# ESP8266.net
KiCad netlist of a schematic drawn in EAGLE
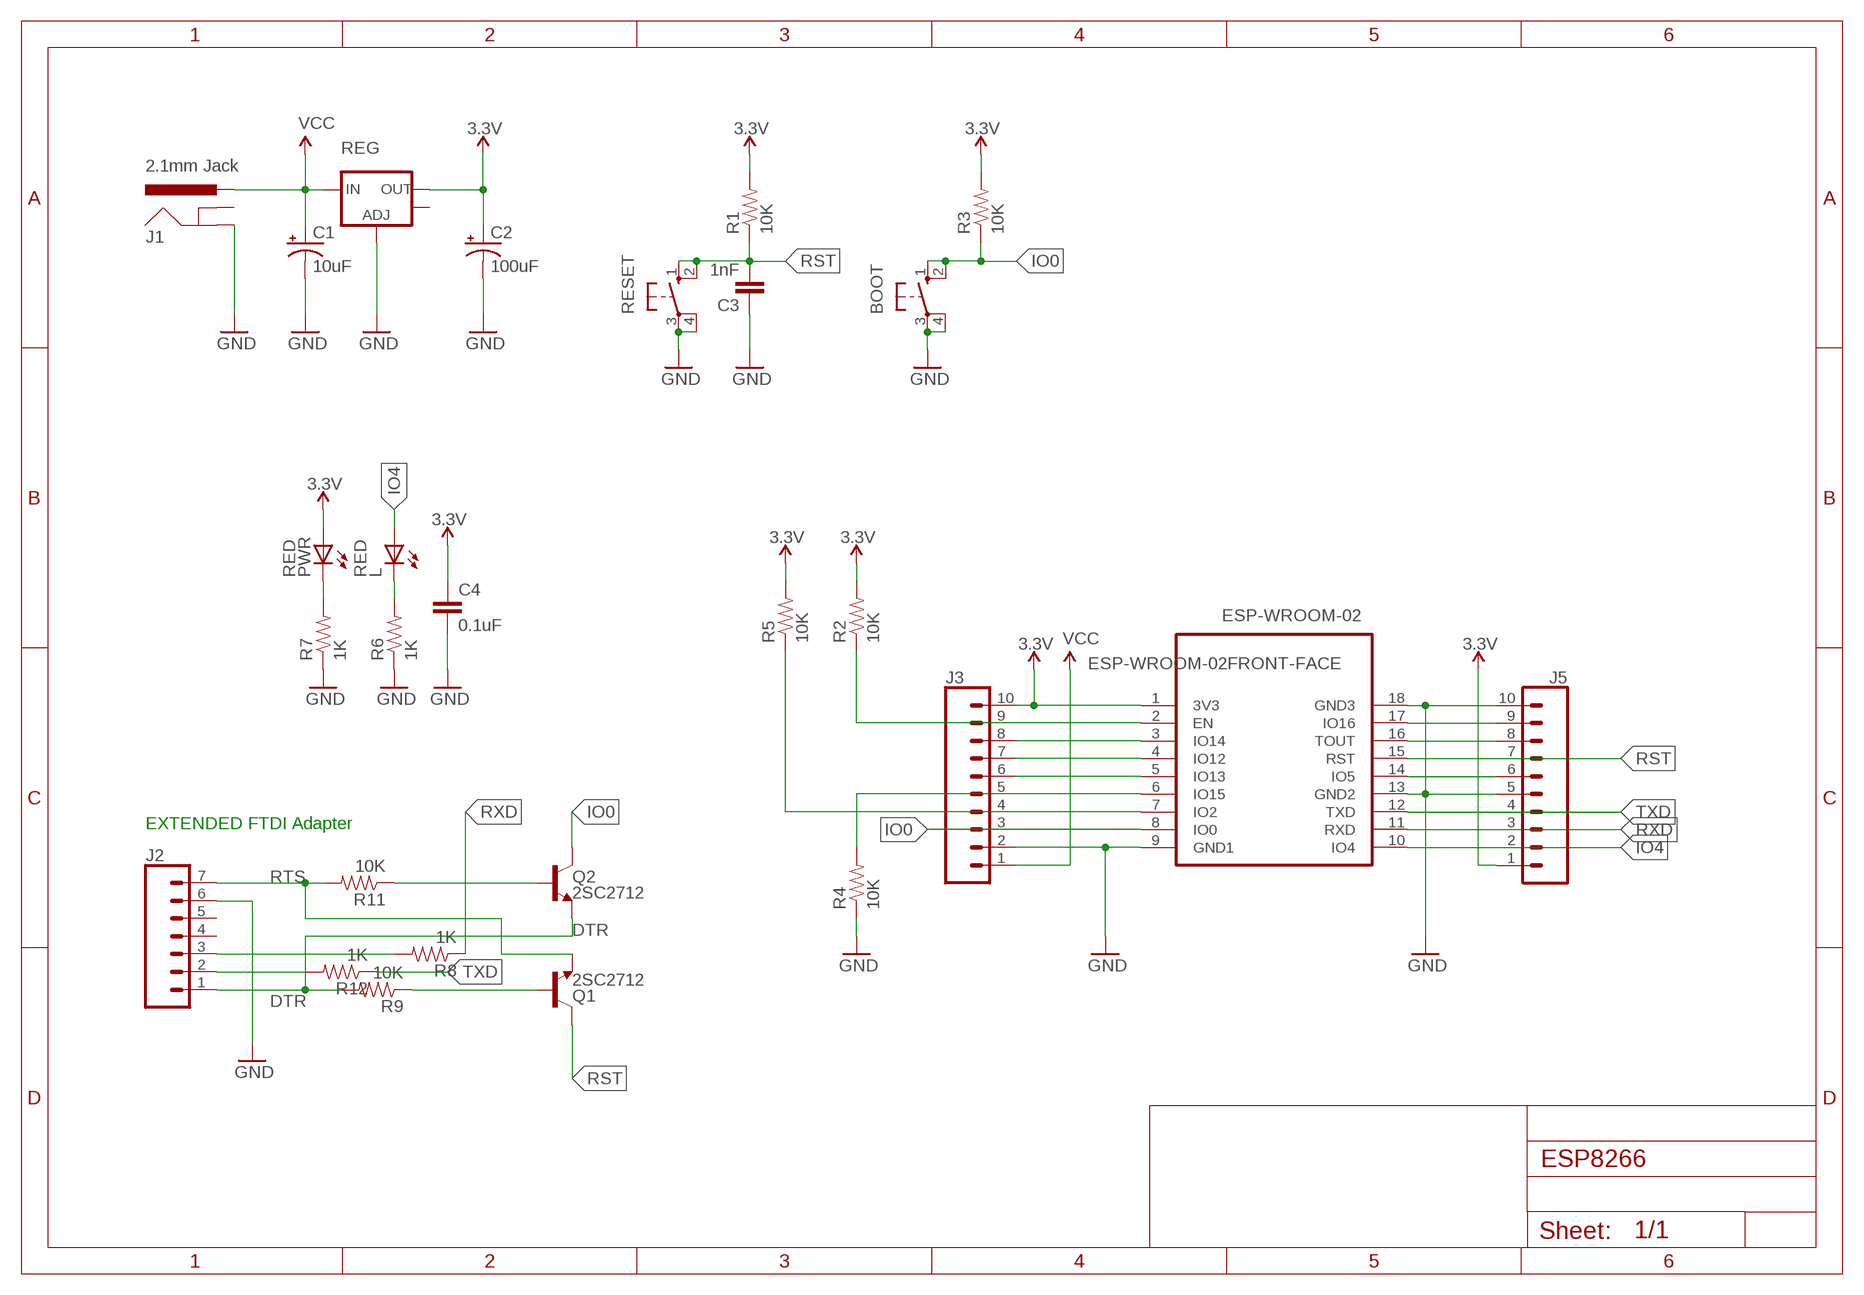
[diagram p0: schematic, sheet 1]

(export (version "E")
  (design (tool "Eeschema 10.0.6"))
  (components
    (comp (ref "BOOT")
      (value "10-XX")
      (footprint "eagle-import:B3F-10XX")
      (libsource (lib "eagle-import") (part "10-XX"))
    )
    (comp (ref "C1")
      (value "10uF")
      (footprint "eagle-import:PANASONIC_D")
      (libsource (lib "eagle-import") (part "CAP_POLD"))
    )
    (comp (ref "C2")
      (value "100uF")
      (footprint "eagle-import:PANASONIC_D")
      (libsource (lib "eagle-import") (part "CAP_POLD"))
    )
    (comp (ref "C3")
      (value "1nF")
      (footprint "eagle-import:0805")
      (libsource (lib "eagle-import") (part "CAP0805"))
    )
    (comp (ref "C4")
      (value "0.1uF")
      (footprint "eagle-import:0805")
      (libsource (lib "eagle-import") (part "CAP0805"))
    )
    (comp (ref "ESP-WROOM-02")
      (value "ESP-WROOM-02FRONT-FACE")
      (footprint "eagle-import:FRONT-FACE")
      (libsource (lib "eagle-import") (part "ESP-WROOM-02FRONT-FACE"))
    )
    (comp (ref "J1")
      (value "2.1mm Jack")
      (footprint "eagle-import:POWER_JACK_PTH_LOCK")
      (libsource (lib "eagle-import") (part "POWER_JACKPTH_LOCK"))
    )
    (comp (ref "J2")
      (value "CONN_07LOCK")
      (footprint "eagle-import:1X07_LOCK")
      (libsource (lib "eagle-import") (part "CONN_07LOCK"))
    )
    (comp (ref "J3")
      (value "CONN_10\"")
      (footprint "eagle-import:1X10")
      (libsource (lib "eagle-import") (part "CONN_10{dblquote}"))
    )
    (comp (ref "J5")
      (value "CONN_10\"")
      (footprint "eagle-import:1X10")
      (libsource (lib "eagle-import") (part "CONN_10{dblquote}"))
    )
    (comp (ref "L")
      (value "RED")
      (footprint "eagle-import:CHIP-LED0805")
      (libsource (lib "eagle-import") (part "LEDCHIP-LED0805"))
    )
    (comp (ref "PWR")
      (value "RED")
      (footprint "eagle-import:CHIP-LED0805")
      (libsource (lib "eagle-import") (part "LEDCHIP-LED0805"))
    )
    (comp (ref "Q1")
      (value "2SC2712")
      (footprint "eagle-import:SOT23-3")
      (libsource (lib "eagle-import") (part "TRANS_NPN-MMBTA42"))
    )
    (comp (ref "Q2")
      (value "2SC2712")
      (footprint "eagle-import:SOT23-3")
      (libsource (lib "eagle-import") (part "TRANS_NPN-MMBTA42"))
    )
    (comp (ref "R1")
      (value "10K")
      (footprint "eagle-import:0805")
      (libsource (lib "eagle-import") (part "RESISTOR0805-RES"))
    )
    (comp (ref "R2")
      (value "10K")
      (footprint "eagle-import:0805")
      (libsource (lib "eagle-import") (part "RESISTOR0805-RES"))
    )
    (comp (ref "R3")
      (value "10K")
      (footprint "eagle-import:0805")
      (libsource (lib "eagle-import") (part "RESISTOR0805-RES"))
    )
    (comp (ref "R4")
      (value "10K")
      (footprint "eagle-import:0805")
      (libsource (lib "eagle-import") (part "RESISTOR0805-RES"))
    )
    (comp (ref "R5")
      (value "10K")
      (footprint "eagle-import:0805")
      (libsource (lib "eagle-import") (part "RESISTOR0805-RES"))
    )
    (comp (ref "R6")
      (value "1K")
      (footprint "eagle-import:0805")
      (libsource (lib "eagle-import") (part "RESISTOR0805-RES"))
    )
    (comp (ref "R7")
      (value "1K")
      (footprint "eagle-import:0805")
      (libsource (lib "eagle-import") (part "RESISTOR0805-RES"))
    )
    (comp (ref "R8")
      (value "1K")
      (footprint "eagle-import:0805")
      (libsource (lib "eagle-import") (part "RESISTOR0805-RES"))
    )
    (comp (ref "R9")
      (value "10K")
      (footprint "eagle-import:0805")
      (libsource (lib "eagle-import") (part "RESISTOR0805-RES"))
    )
    (comp (ref "R11")
      (value "10K")
      (footprint "eagle-import:0805")
      (libsource (lib "eagle-import") (part "RESISTOR0805-RES"))
    )
    (comp (ref "R12")
      (value "1K")
      (footprint "eagle-import:0805")
      (libsource (lib "eagle-import") (part "RESISTOR0805-RES"))
    )
    (comp (ref "REG")
      (value "V_REG_LM1117SOT223")
      (footprint "eagle-import:SOT223")
      (libsource (lib "eagle-import") (part "V_REG_LM1117SOT223"))
    )
    (comp (ref "RESET")
      (value "10-XX")
      (footprint "eagle-import:B3F-10XX")
      (libsource (lib "eagle-import") (part "10-XX"))
    )
  )
  (nets
    (net (code "1") (name "/DTR") (class "Default")
      (node (ref "J2") (pin "1") (pinfunction "1_1") (pintype "passive"))
      (node (ref "Q2") (pin "2") (pinfunction "E_2") (pintype "passive"))
      (node (ref "R9") (pin "2") (pinfunction "2_2") (pintype "passive"))
    )
    (net (code "2") (name "/RTS") (class "Default")
      (node (ref "J2") (pin "7") (pinfunction "7_7") (pintype "passive"))
      (node (ref "Q1") (pin "2") (pinfunction "E_2") (pintype "passive"))
      (node (ref "R11") (pin "2") (pinfunction "2_2") (pintype "passive"))
    )
    (net (code "3") (name "3.3V") (class "Default")
      (node (ref "C2") (pin "+") (pinfunction "+_+") (pintype "passive"))
      (node (ref "C4") (pin "1") (pinfunction "1_1") (pintype "passive"))
      (node (ref "ESP-WROOM-02") (pin "1") (pinfunction "3V3_1") (pintype "power_in"))
      (node (ref "J3") (pin "10") (pinfunction "10_10") (pintype "passive"))
      (node (ref "J5") (pin "1") (pinfunction "1_1") (pintype "passive"))
      (node (ref "PWR") (pin "A") (pinfunction "A_A") (pintype "passive"))
      (node (ref "R1") (pin "2") (pinfunction "2_2") (pintype "passive"))
      (node (ref "R2") (pin "2") (pinfunction "2_2") (pintype "passive"))
      (node (ref "R3") (pin "2") (pinfunction "2_2") (pintype "passive"))
      (node (ref "R5") (pin "2") (pinfunction "2_2") (pintype "passive"))
      (node (ref "REG") (pin "2") (pinfunction "OUT_2") (pintype "output"))
    )
    (net (code "4") (name "GND") (class "Default")
      (node (ref "BOOT") (pin "3") (pinfunction "P_3") (pintype "passive"))
      (node (ref "BOOT") (pin "4") (pinfunction "P1_4") (pintype "passive"))
      (node (ref "C1") (pin "-") (pinfunction "-_-") (pintype "passive"))
      (node (ref "C2") (pin "-") (pinfunction "-_-") (pintype "passive"))
      (node (ref "C3") (pin "1") (pinfunction "1_1") (pintype "passive"))
      (node (ref "C4") (pin "2") (pinfunction "2_2") (pintype "passive"))
      (node (ref "ESP-WROOM-02") (pin "13") (pinfunction "GND2_13") (pintype "power_in"))
      (node (ref "ESP-WROOM-02") (pin "18") (pinfunction "GND3_18") (pintype "power_in"))
      (node (ref "ESP-WROOM-02") (pin "9") (pinfunction "GND1_9") (pintype "power_in"))
      (node (ref "J1") (pin "GND") (pinfunction "GND_GND") (pintype "bidirectional"))
      (node (ref "J2") (pin "6") (pinfunction "6_6") (pintype "passive"))
      (node (ref "J3") (pin "2") (pinfunction "2_2") (pintype "passive"))
      (node (ref "J5") (pin "10") (pinfunction "10_10") (pintype "passive"))
      (node (ref "J5") (pin "5") (pinfunction "5_5") (pintype "passive"))
      (node (ref "R4") (pin "1") (pinfunction "1_1") (pintype "passive"))
      (node (ref "R6") (pin "1") (pinfunction "1_1") (pintype "passive"))
      (node (ref "R7") (pin "1") (pinfunction "1_1") (pintype "passive"))
      (node (ref "REG") (pin "1") (pinfunction "ADJ_1") (pintype "input"))
      (node (ref "RESET") (pin "3") (pinfunction "P_3") (pintype "passive"))
      (node (ref "RESET") (pin "4") (pinfunction "P1_4") (pintype "passive"))
    )
    (net (code "5") (name "IO0") (class "Default")
      (node (ref "BOOT") (pin "1") (pinfunction "S_1") (pintype "passive"))
      (node (ref "BOOT") (pin "2") (pinfunction "S1_2") (pintype "passive"))
      (node (ref "ESP-WROOM-02") (pin "8") (pinfunction "IO0_8") (pintype "bidirectional"))
      (node (ref "J3") (pin "3") (pinfunction "3_3") (pintype "passive"))
      (node (ref "Q2") (pin "3") (pinfunction "C_3") (pintype "passive"))
      (node (ref "R3") (pin "1") (pinfunction "1_1") (pintype "passive"))
    )
    (net (code "6") (name "IO4") (class "Default")
      (node (ref "ESP-WROOM-02") (pin "10") (pinfunction "IO4_10") (pintype "bidirectional"))
      (node (ref "J5") (pin "2") (pinfunction "2_2") (pintype "passive"))
      (node (ref "L") (pin "A") (pinfunction "A_A") (pintype "passive"))
    )
    (net (code "7") (name "Net-(ESP-WROOM-02-EN)") (class "Default")
      (node (ref "ESP-WROOM-02") (pin "2") (pinfunction "EN_2") (pintype "bidirectional"))
      (node (ref "J3") (pin "9") (pinfunction "9_9") (pintype "passive"))
      (node (ref "R2") (pin "1") (pinfunction "1_1") (pintype "passive"))
    )
    (net (code "8") (name "Net-(ESP-WROOM-02-IO2)") (class "Default")
      (node (ref "ESP-WROOM-02") (pin "7") (pinfunction "IO2_7") (pintype "bidirectional"))
      (node (ref "J3") (pin "4") (pinfunction "4_4") (pintype "passive"))
      (node (ref "R5") (pin "1") (pinfunction "1_1") (pintype "passive"))
    )
    (net (code "9") (name "Net-(ESP-WROOM-02-IO5)") (class "Default")
      (node (ref "ESP-WROOM-02") (pin "14") (pinfunction "IO5_14") (pintype "open_collector"))
      (node (ref "J5") (pin "6") (pinfunction "6_6") (pintype "passive"))
    )
    (net (code "10") (name "Net-(ESP-WROOM-02-IO12)") (class "Default")
      (node (ref "ESP-WROOM-02") (pin "4") (pinfunction "IO12_4") (pintype "bidirectional"))
      (node (ref "J3") (pin "7") (pinfunction "7_7") (pintype "passive"))
    )
    (net (code "11") (name "Net-(ESP-WROOM-02-IO13)") (class "Default")
      (node (ref "ESP-WROOM-02") (pin "5") (pinfunction "IO13_5") (pintype "bidirectional"))
      (node (ref "J3") (pin "6") (pinfunction "6_6") (pintype "passive"))
    )
    (net (code "12") (name "Net-(ESP-WROOM-02-IO14)") (class "Default")
      (node (ref "ESP-WROOM-02") (pin "3") (pinfunction "IO14_3") (pintype "bidirectional"))
      (node (ref "J3") (pin "8") (pinfunction "8_8") (pintype "passive"))
    )
    (net (code "13") (name "Net-(ESP-WROOM-02-IO15)") (class "Default")
      (node (ref "ESP-WROOM-02") (pin "6") (pinfunction "IO15_6") (pintype "bidirectional"))
      (node (ref "J3") (pin "5") (pinfunction "5_5") (pintype "passive"))
      (node (ref "R4") (pin "2") (pinfunction "2_2") (pintype "passive"))
    )
    (net (code "14") (name "Net-(ESP-WROOM-02-IO16)") (class "Default")
      (node (ref "ESP-WROOM-02") (pin "17") (pinfunction "IO16_17") (pintype "bidirectional"))
      (node (ref "J5") (pin "9") (pinfunction "9_9") (pintype "passive"))
    )
    (net (code "15") (name "Net-(ESP-WROOM-02-TOUT)") (class "Default")
      (node (ref "ESP-WROOM-02") (pin "16") (pinfunction "TOUT_16") (pintype "bidirectional"))
      (node (ref "J5") (pin "8") (pinfunction "8_8") (pintype "passive"))
    )
    (net (code "16") (name "Net-(J2-Pad2)") (class "Default")
      (node (ref "J2") (pin "2") (pinfunction "2_2") (pintype "passive"))
      (node (ref "R12") (pin "2") (pinfunction "2_2") (pintype "passive"))
    )
    (net (code "17") (name "Net-(J2-Pad3)") (class "Default")
      (node (ref "J2") (pin "3") (pinfunction "3_3") (pintype "passive"))
      (node (ref "R8") (pin "2") (pinfunction "2_2") (pintype "passive"))
    )
    (net (code "18") (name "Net-(L-PadC)") (class "Default")
      (node (ref "L") (pin "C") (pinfunction "C_C") (pintype "passive"))
      (node (ref "R6") (pin "2") (pinfunction "2_2") (pintype "passive"))
    )
    (net (code "19") (name "Net-(PWR-PadC)") (class "Default")
      (node (ref "PWR") (pin "C") (pinfunction "C_C") (pintype "passive"))
      (node (ref "R7") (pin "2") (pinfunction "2_2") (pintype "passive"))
    )
    (net (code "20") (name "Net-(Q1-B)") (class "Default")
      (node (ref "Q1") (pin "1") (pinfunction "B_1") (pintype "passive"))
      (node (ref "R9") (pin "1") (pinfunction "1_1") (pintype "passive"))
    )
    (net (code "21") (name "Net-(Q2-B)") (class "Default")
      (node (ref "Q2") (pin "1") (pinfunction "B_1") (pintype "passive"))
      (node (ref "R11") (pin "1") (pinfunction "1_1") (pintype "passive"))
    )
    (net (code "22") (name "RST") (class "Default")
      (node (ref "C3") (pin "2") (pinfunction "2_2") (pintype "passive"))
      (node (ref "ESP-WROOM-02") (pin "15") (pinfunction "RST_15") (pintype "bidirectional"))
      (node (ref "J5") (pin "7") (pinfunction "7_7") (pintype "passive"))
      (node (ref "Q1") (pin "3") (pinfunction "C_3") (pintype "passive"))
      (node (ref "R1") (pin "1") (pinfunction "1_1") (pintype "passive"))
      (node (ref "RESET") (pin "1") (pinfunction "S_1") (pintype "passive"))
      (node (ref "RESET") (pin "2") (pinfunction "S1_2") (pintype "passive"))
    )
    (net (code "23") (name "RXD") (class "Default")
      (node (ref "ESP-WROOM-02") (pin "11") (pinfunction "RXD_11") (pintype "bidirectional"))
      (node (ref "J5") (pin "3") (pinfunction "3_3") (pintype "passive"))
      (node (ref "R8") (pin "1") (pinfunction "1_1") (pintype "passive"))
    )
    (net (code "24") (name "TXD") (class "Default")
      (node (ref "ESP-WROOM-02") (pin "12") (pinfunction "TXD_12") (pintype "bidirectional"))
      (node (ref "J5") (pin "4") (pinfunction "4_4") (pintype "passive"))
      (node (ref "R12") (pin "1") (pinfunction "1_1") (pintype "passive"))
    )
    (net (code "25") (name "VCC") (class "Default")
      (node (ref "C1") (pin "+") (pinfunction "+_+") (pintype "passive"))
      (node (ref "J1") (pin "PWR") (pinfunction "PWR_PWR") (pintype "bidirectional"))
      (node (ref "J3") (pin "1") (pinfunction "1_1") (pintype "passive"))
      (node (ref "REG") (pin "3") (pinfunction "IN_3") (pintype "input"))
    )
    (net (code "26") (name "unconnected-(J1-PadGNDBREAK)") (class "Default")
      (node (ref "J1") (pin "GNDBREAK") (pinfunction "GNDBREAK_GNDBREAK") (pintype "bidirectional"))
    )
    (net (code "27") (name "unconnected-(J2-Pad4)") (class "Default")
      (node (ref "J2") (pin "4") (pinfunction "4_4") (pintype "passive"))
    )
    (net (code "28") (name "unconnected-(J2-Pad5)") (class "Default")
      (node (ref "J2") (pin "5") (pinfunction "5_5") (pintype "passive"))
    )
    (net (code "29") (name "unconnected-(REG-OUT-Pad4)") (class "Default")
      (node (ref "REG") (pin "4") (pinfunction "OUT_4") (pintype "output"))
    )
  )
)
